# test-aetzen.net
KiCad netlist of a schematic drawn in EAGLE
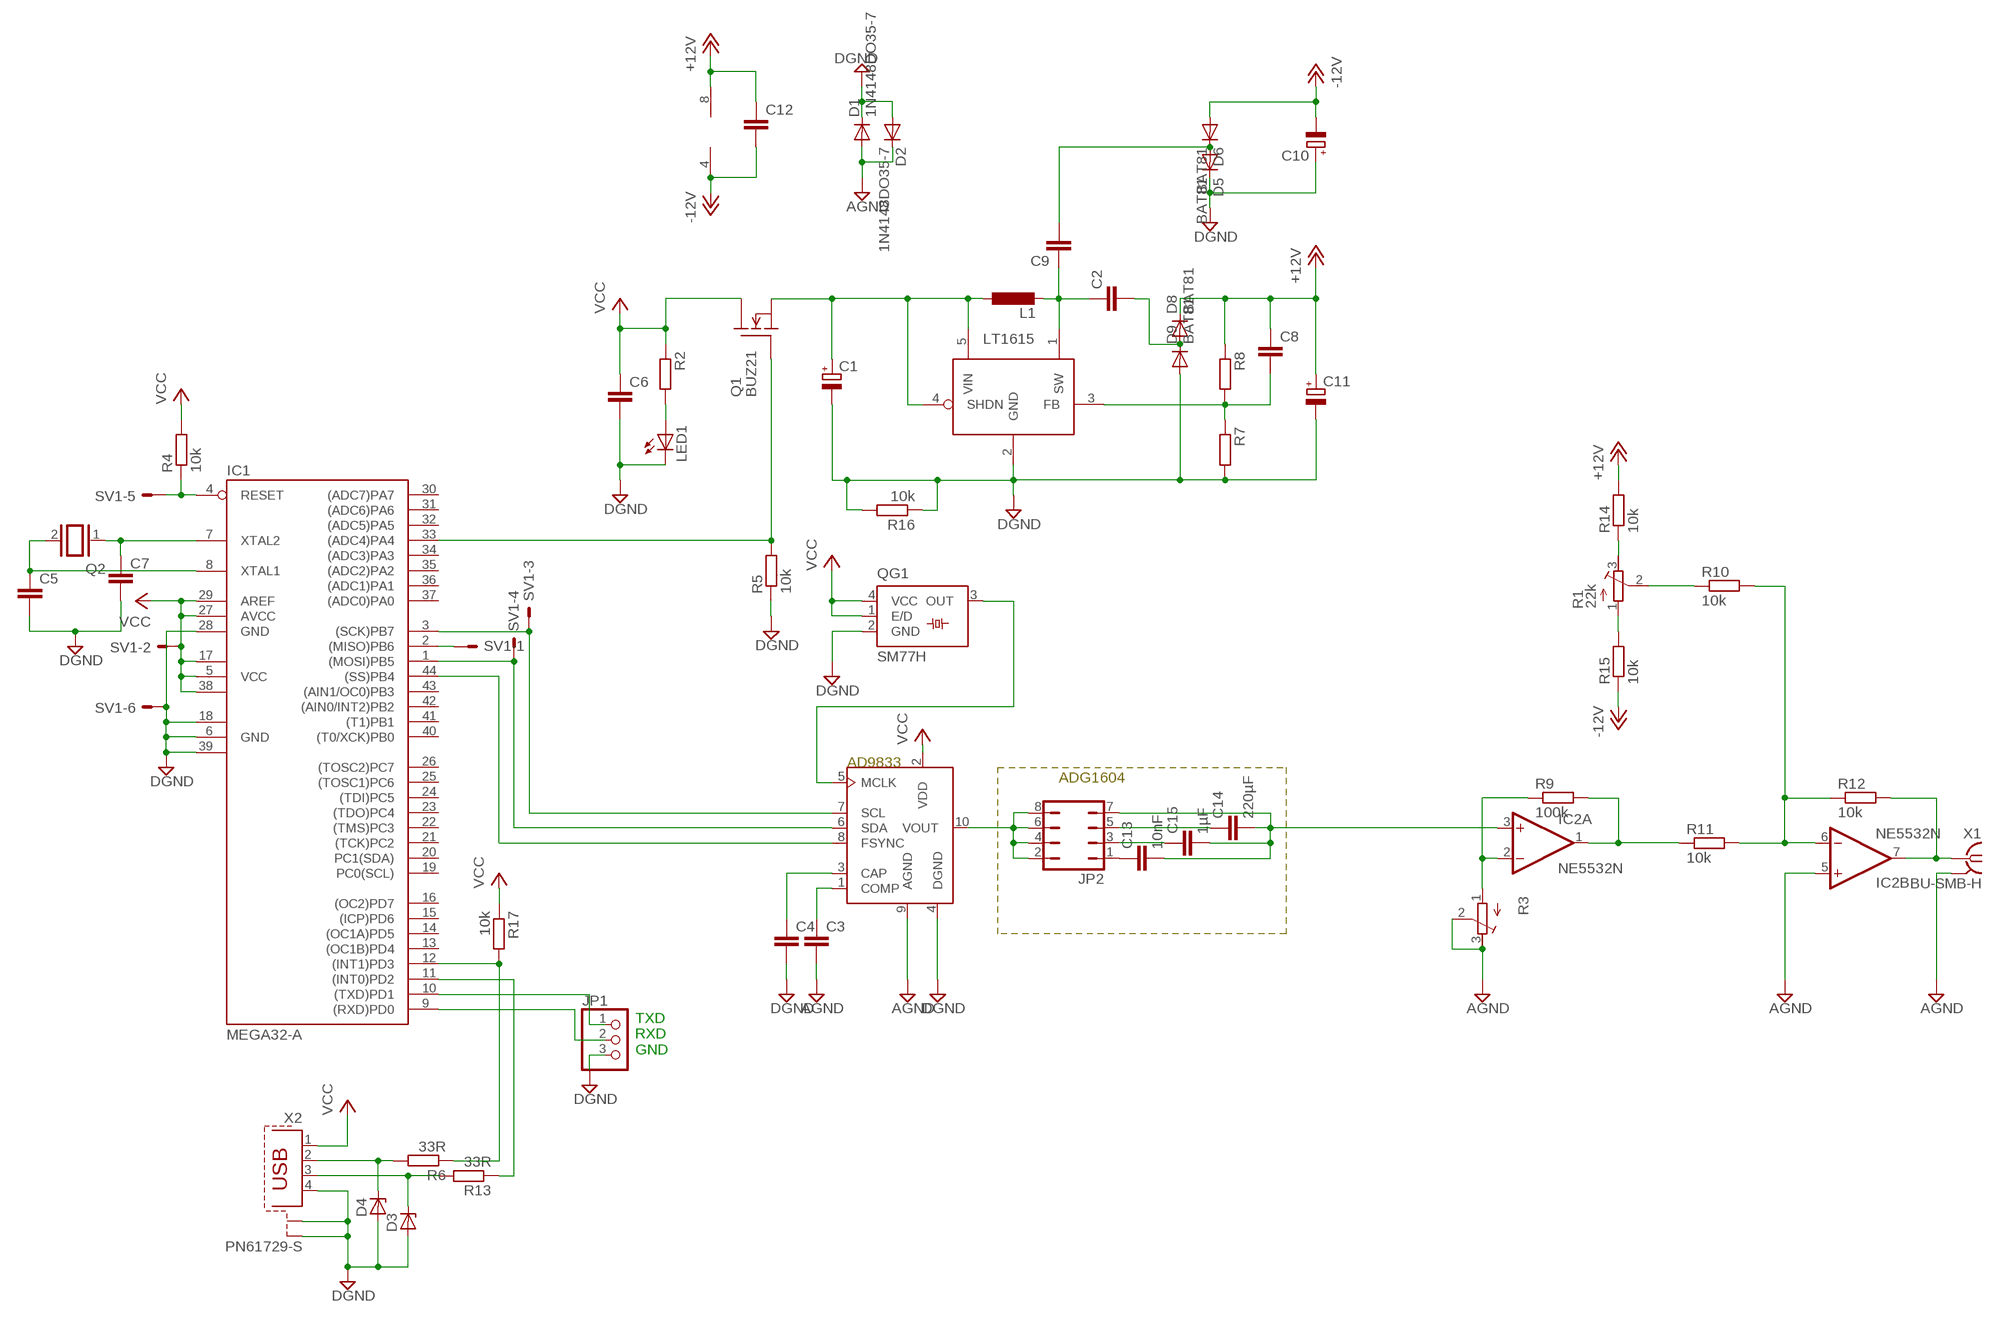
[diagram p0: schematic, sheet 1]

(export (version "E")
  (design (tool "Eeschema 10.0.6"))
  (components
    (comp (ref "C1")
      (value "CPOL-EUE3.5-8")
      (footprint "eagle-import:E3,5-8")
      (libsource (lib "eagle-import") (part "CPOL-EUE3.5-8"))
    )
    (comp (ref "C2")
      (value "C-EU025-024X044")
      (footprint "eagle-import:C025-024X044")
      (libsource (lib "eagle-import") (part "C-EU025-024X044"))
    )
    (comp (ref "C3")
      (value "C-EU025-024X044")
      (footprint "eagle-import:C025-024X044")
      (libsource (lib "eagle-import") (part "C-EU025-024X044"))
    )
    (comp (ref "C4")
      (value "C-EU025-024X044")
      (footprint "eagle-import:C025-024X044")
      (libsource (lib "eagle-import") (part "C-EU025-024X044"))
    )
    (comp (ref "C5")
      (value "C-EU025-024X044")
      (footprint "eagle-import:C025-024X044")
      (libsource (lib "eagle-import") (part "C-EU025-024X044"))
    )
    (comp (ref "C6")
      (value "C-EU025-024X044")
      (footprint "eagle-import:C025-024X044")
      (libsource (lib "eagle-import") (part "C-EU025-024X044"))
    )
    (comp (ref "C7")
      (value "C-EU025-024X044")
      (footprint "eagle-import:C025-024X044")
      (libsource (lib "eagle-import") (part "C-EU025-024X044"))
    )
    (comp (ref "C8")
      (value "C-EU025-024X044")
      (footprint "eagle-import:C025-024X044")
      (libsource (lib "eagle-import") (part "C-EU025-024X044"))
    )
    (comp (ref "C9")
      (value "C-EU025-024X044")
      (footprint "eagle-import:C025-024X044")
      (libsource (lib "eagle-import") (part "C-EU025-024X044"))
    )
    (comp (ref "C10")
      (value "CPOL-EUE3.5-8")
      (footprint "eagle-import:E3,5-8")
      (libsource (lib "eagle-import") (part "CPOL-EUE3.5-8"))
    )
    (comp (ref "C11")
      (value "CPOL-EUE3.5-8")
      (footprint "eagle-import:E3,5-8")
      (libsource (lib "eagle-import") (part "CPOL-EUE3.5-8"))
    )
    (comp (ref "C12")
      (value "C-EU025-024X044")
      (footprint "eagle-import:C025-024X044")
      (libsource (lib "eagle-import") (part "C-EU025-024X044"))
    )
    (comp (ref "C13")
      (value "10nF")
      (footprint "eagle-import:C025-024X044")
      (libsource (lib "eagle-import") (part "C-EU025-024X044"))
    )
    (comp (ref "C14")
      (value "220µF")
      (footprint "eagle-import:C025-024X044")
      (libsource (lib "eagle-import") (part "C-EU025-024X044"))
    )
    (comp (ref "C15")
      (value "1µF")
      (footprint "eagle-import:C025-024X044")
      (libsource (lib "eagle-import") (part "C-EU025-024X044"))
    )
    (comp (ref "D1")
      (value "1N4148DO35-7")
      (footprint "eagle-import:DO35-7")
      (libsource (lib "eagle-import") (part "1N4148DO35-7"))
    )
    (comp (ref "D2")
      (value "1N4148DO35-7")
      (footprint "eagle-import:DO35-7")
      (libsource (lib "eagle-import") (part "1N4148DO35-7"))
    )
    (comp (ref "D3")
      (value "ZENER-DIODEDO35Z10")
      (footprint "eagle-import:DO35Z10")
      (libsource (lib "eagle-import") (part "ZENER-DIODEDO35Z10"))
    )
    (comp (ref "D4")
      (value "ZENER-DIODEDO35Z10")
      (footprint "eagle-import:DO35Z10")
      (libsource (lib "eagle-import") (part "ZENER-DIODEDO35Z10"))
    )
    (comp (ref "D5")
      (value "BAT81")
      (footprint "eagle-import:DO34-7")
      (libsource (lib "eagle-import") (part "BAT81"))
    )
    (comp (ref "D6")
      (value "BAT81")
      (footprint "eagle-import:DO34-7")
      (libsource (lib "eagle-import") (part "BAT81"))
    )
    (comp (ref "D8")
      (value "BAT81")
      (footprint "eagle-import:DO34-7")
      (libsource (lib "eagle-import") (part "BAT81"))
    )
    (comp (ref "D9")
      (value "BAT81")
      (footprint "eagle-import:DO34-7")
      (libsource (lib "eagle-import") (part "BAT81"))
    )
    (comp (ref "IC1")
      (value "MEGA32-A")
      (footprint "eagle-import:TQFP44")
      (fields (field (name "MPN") "ATMEGA32-16AU"))
      (libsource (lib "eagle-import") (part "MEGA32-A"))
    )
    (comp (ref "IC2")
      (value "NE5532N")
      (footprint "eagle-import:DIL08")
      (libsource (lib "eagle-import") (part "NE5532N"))
    )
    (comp (ref "JP1")
      (value "PINHD-1X3")
      (footprint "eagle-import:1X03")
      (libsource (lib "eagle-import") (part "PINHD-1X3"))
    )
    (comp (ref "JP2")
      (value "JP4Q")
      (footprint "eagle-import:JP4Q")
      (libsource (lib "eagle-import") (part "JP4Q"))
    )
    (comp (ref "L1")
      (value "L-EU0207/10")
      (footprint "eagle-import:0207_10")
      (libsource (lib "eagle-import") (part "L-EU0207/10"))
    )
    (comp (ref "LED1")
      (value "LED5MM")
      (footprint "eagle-import:LED5MM")
      (libsource (lib "eagle-import") (part "LED5MM"))
    )
    (comp (ref "Q1")
      (value "BUZ21")
      (footprint "eagle-import:TO220V")
      (libsource (lib "eagle-import") (part "BUZ21"))
    )
    (comp (ref "Q2")
      (value "XTAL/S")
      (footprint "eagle-import:QS")
      (libsource (lib "eagle-import") (part "XTAL/S"))
    )
    (comp (ref "QG1")
      (value "SM77H")
      (footprint "eagle-import:SM77H")
      (libsource (lib "eagle-import") (part "SM77H"))
    )
    (comp (ref "R1")
      (value "22k")
      (footprint "eagle-import:RTRIM64Y")
      (libsource (lib "eagle-import") (part "R-TRIMM64Y"))
    )
    (comp (ref "R2")
      (value "R-EU_0207/10")
      (footprint "eagle-import:0207_10")
      (libsource (lib "eagle-import") (part "R-EU_0207/10"))
    )
    (comp (ref "R3")
      (value "R-TRIMM64Y")
      (footprint "eagle-import:RTRIM64Y")
      (libsource (lib "eagle-import") (part "R-TRIMM64Y"))
    )
    (comp (ref "R4")
      (value "10k")
      (footprint "eagle-import:M1206")
      (libsource (lib "eagle-import") (part "R-EU_M1206"))
    )
    (comp (ref "R5")
      (value "10k")
      (footprint "eagle-import:M1206")
      (libsource (lib "eagle-import") (part "R-EU_M1206"))
    )
    (comp (ref "R6")
      (value "33R")
      (footprint "eagle-import:0207_10")
      (libsource (lib "eagle-import") (part "R-EU_0207/10"))
    )
    (comp (ref "R7")
      (value "R-EU_0207/10")
      (footprint "eagle-import:0207_10")
      (libsource (lib "eagle-import") (part "R-EU_0207/10"))
    )
    (comp (ref "R8")
      (value "R-EU_0207/10")
      (footprint "eagle-import:0207_10")
      (libsource (lib "eagle-import") (part "R-EU_0207/10"))
    )
    (comp (ref "R9")
      (value "100k")
      (footprint "eagle-import:0207_10")
      (libsource (lib "eagle-import") (part "R-EU_0207/10"))
    )
    (comp (ref "R10")
      (value "10k")
      (footprint "eagle-import:M1206")
      (libsource (lib "eagle-import") (part "R-EU_M1206"))
    )
    (comp (ref "R11")
      (value "10k")
      (footprint "eagle-import:M1206")
      (libsource (lib "eagle-import") (part "R-EU_M1206"))
    )
    (comp (ref "R12")
      (value "10k")
      (footprint "eagle-import:M1206")
      (libsource (lib "eagle-import") (part "R-EU_M1206"))
    )
    (comp (ref "R13")
      (value "33R")
      (footprint "eagle-import:0207_10")
      (libsource (lib "eagle-import") (part "R-EU_0207/10"))
    )
    (comp (ref "R14")
      (value "10k")
      (footprint "eagle-import:M1206")
      (libsource (lib "eagle-import") (part "R-EU_M1206"))
    )
    (comp (ref "R15")
      (value "10k")
      (footprint "eagle-import:M1206")
      (libsource (lib "eagle-import") (part "R-EU_M1206"))
    )
    (comp (ref "R16")
      (value "10k")
      (footprint "eagle-import:M1206")
      (libsource (lib "eagle-import") (part "R-EU_M1206"))
    )
    (comp (ref "R17")
      (value "10k")
      (footprint "eagle-import:M1206")
      (libsource (lib "eagle-import") (part "R-EU_M1206"))
    )
    (comp (ref "SV1")
      (value "ML6E")
      (footprint "eagle-import:ML6")
      (libsource (lib "eagle-import") (part "ML6?E"))
    )
    (comp (ref "U$1")
      (value "AD9833-P")
      (footprint "eagle-import:DIL10")
      (libsource (lib "eagle-import") (part "AD9833-P"))
    )
    (comp (ref "U$2")
      (value "LT1615")
      (footprint "eagle-import:SOT23-5")
      (libsource (lib "eagle-import") (part "LT1615"))
    )
    (comp (ref "X1")
      (value "BU-SMB-H")
      (footprint "eagle-import:BU-SMB-H")
      (libsource (lib "eagle-import") (part "BU-SMB-H"))
    )
    (comp (ref "X2")
      (value "PN61729-S")
      (footprint "eagle-import:PN61729-S")
      (libsource (lib "eagle-import") (part "PN61729-S"))
    )
  )
  (nets
    (net (code "1") (name "+12V") (class "Default")
      (node (ref "C11") (pin "+") (pinfunction "+_+") (pintype "passive"))
      (node (ref "C12") (pin "1") (pinfunction "1_1") (pintype "passive"))
      (node (ref "C8") (pin "1") (pinfunction "1_1") (pintype "passive"))
      (node (ref "D8") (pin "C") (pinfunction "C_C") (pintype "passive"))
      (node (ref "IC2") (pin "8") (pinfunction "V+_8") (pintype "power_in"))
      (node (ref "R14") (pin "2") (pinfunction "2_2") (pintype "passive"))
      (node (ref "R8") (pin "1") (pinfunction "1_1") (pintype "passive"))
    )
    (net (code "2") (name "-12V") (class "Default")
      (node (ref "C10") (pin "-") (pinfunction "-_-") (pintype "passive"))
      (node (ref "C12") (pin "2") (pinfunction "2_2") (pintype "passive"))
      (node (ref "D6") (pin "A") (pinfunction "A_A") (pintype "passive"))
      (node (ref "IC2") (pin "4") (pinfunction "V-_4") (pintype "power_in"))
      (node (ref "R15") (pin "1") (pinfunction "1_1") (pintype "passive"))
    )
    (net (code "3") (name "AGND") (class "Default")
      (node (ref "C3") (pin "2") (pinfunction "2_2") (pintype "passive"))
      (node (ref "D1") (pin "A") (pinfunction "A_A") (pintype "passive"))
      (node (ref "D2") (pin "C") (pinfunction "C_C") (pintype "passive"))
      (node (ref "IC2") (pin "5") (pinfunction "+IN_5") (pintype "input"))
      (node (ref "R3") (pin "2") (pinfunction "S_2") (pintype "passive"))
      (node (ref "R3") (pin "3") (pinfunction "E_3") (pintype "passive"))
      (node (ref "U$1") (pin "9") (pinfunction "AGND_9") (pintype "bidirectional"))
      (node (ref "X1") (pin "2") (pinfunction "2_2") (pintype "passive"))
      (node (ref "X1") (pin "3") (pinfunction "2_3") (pintype "passive"))
      (node (ref "X1") (pin "4") (pinfunction "2_4") (pintype "passive"))
      (node (ref "X1") (pin "5") (pinfunction "2_5") (pintype "passive"))
    )
    (net (code "4") (name "DGND") (class "Default")
      (node (ref "C1") (pin "-") (pinfunction "-_-") (pintype "passive"))
      (node (ref "C10") (pin "+") (pinfunction "+_+") (pintype "passive"))
      (node (ref "C11") (pin "-") (pinfunction "-_-") (pintype "passive"))
      (node (ref "C4") (pin "2") (pinfunction "2_2") (pintype "passive"))
      (node (ref "C5") (pin "2") (pinfunction "2_2") (pintype "passive"))
      (node (ref "C6") (pin "2") (pinfunction "2_2") (pintype "passive"))
      (node (ref "C7") (pin "2") (pinfunction "2_2") (pintype "passive"))
      (node (ref "D1") (pin "C") (pinfunction "C_C") (pintype "passive"))
      (node (ref "D2") (pin "A") (pinfunction "A_A") (pintype "passive"))
      (node (ref "D3") (pin "A") (pinfunction "A_A") (pintype "passive"))
      (node (ref "D4") (pin "A") (pinfunction "A_A") (pintype "passive"))
      (node (ref "D5") (pin "C") (pinfunction "C_C") (pintype "passive"))
      (node (ref "D9") (pin "A") (pinfunction "A_A") (pintype "passive"))
      (node (ref "IC1") (pin "18") (pinfunction "GND1_18") (pintype "power_in"))
      (node (ref "IC1") (pin "28") (pinfunction "GND_28") (pintype "power_in"))
      (node (ref "IC1") (pin "39") (pinfunction "GND2_39") (pintype "power_in"))
      (node (ref "IC1") (pin "6") (pinfunction "GND_6") (pintype "power_in"))
      (node (ref "JP1") (pin "3") (pinfunction "3_3") (pintype "passive"))
      (node (ref "LED1") (pin "K") (pinfunction "C_K") (pintype "passive"))
      (node (ref "QG1") (pin "2") (pinfunction "GND_2") (pintype "power_in"))
      (node (ref "R16") (pin "1") (pinfunction "1_1") (pintype "passive"))
      (node (ref "R16") (pin "2") (pinfunction "2_2") (pintype "passive"))
      (node (ref "R5") (pin "1") (pinfunction "1_1") (pintype "passive"))
      (node (ref "R7") (pin "2") (pinfunction "2_2") (pintype "passive"))
      (node (ref "SV1") (pin "6") (pinfunction "S_6") (pintype "passive"))
      (node (ref "U$1") (pin "4") (pinfunction "DGND_4") (pintype "bidirectional"))
      (node (ref "U$2") (pin "2") (pinfunction "GND_2") (pintype "bidirectional"))
      (node (ref "X2") (pin "4") (pinfunction "4_4") (pintype "passive"))
      (node (ref "X2") (pin "S1") (pinfunction "S1_S1") (pintype "passive"))
      (node (ref "X2") (pin "S2") (pinfunction "S2_S2") (pintype "passive"))
    )
    (net (code "5") (name "Net-(C2-Pad2)") (class "Default")
      (node (ref "C2") (pin "2") (pinfunction "2_2") (pintype "passive"))
      (node (ref "D8") (pin "A") (pinfunction "A_A") (pintype "passive"))
      (node (ref "D9") (pin "C") (pinfunction "C_C") (pintype "passive"))
    )
    (net (code "6") (name "Net-(C9-Pad2)") (class "Default")
      (node (ref "C9") (pin "2") (pinfunction "2_2") (pintype "passive"))
      (node (ref "D5") (pin "A") (pinfunction "A_A") (pintype "passive"))
      (node (ref "D6") (pin "C") (pinfunction "C_C") (pintype "passive"))
    )
    (net (code "7") (name "Net-(C13-Pad1)") (class "Default")
      (node (ref "C13") (pin "1") (pinfunction "1_1") (pintype "passive"))
      (node (ref "JP2") (pin "1") (pinfunction "1_1") (pintype "passive"))
    )
    (net (code "8") (name "Net-(C14-Pad1)") (class "Default")
      (node (ref "C14") (pin "1") (pinfunction "1_1") (pintype "passive"))
      (node (ref "JP2") (pin "5") (pinfunction "5_5") (pintype "passive"))
    )
    (net (code "9") (name "Net-(C15-Pad1)") (class "Default")
      (node (ref "C15") (pin "1") (pinfunction "1_1") (pintype "passive"))
      (node (ref "JP2") (pin "3") (pinfunction "3_3") (pintype "passive"))
    )
    (net (code "10") (name "Net-(D3-PadC)") (class "Default")
      (node (ref "D3") (pin "C") (pinfunction "C_C") (pintype "passive"))
      (node (ref "R13") (pin "2") (pinfunction "2_2") (pintype "passive"))
      (node (ref "X2") (pin "3") (pinfunction "3_3") (pintype "passive"))
    )
    (net (code "11") (name "Net-(D4-PadC)") (class "Default")
      (node (ref "D4") (pin "C") (pinfunction "C_C") (pintype "passive"))
      (node (ref "R6") (pin "2") (pinfunction "2_2") (pintype "passive"))
      (node (ref "X2") (pin "2") (pinfunction "2_2") (pintype "passive"))
    )
    (net (code "12") (name "Net-(IC1-(ADC4)PA4)") (class "Default")
      (node (ref "IC1") (pin "33") (pinfunction "(ADC4)PA4_33") (pintype "bidirectional"))
      (node (ref "Q1") (pin "1") (pinfunction "G_1") (pintype "passive"))
      (node (ref "R5") (pin "2") (pinfunction "2_2") (pintype "passive"))
    )
    (net (code "13") (name "Net-(IC1-(INT0)PD2)") (class "Default")
      (node (ref "IC1") (pin "11") (pinfunction "(INT0)PD2_11") (pintype "bidirectional"))
      (node (ref "R13") (pin "1") (pinfunction "1_1") (pintype "passive"))
    )
    (net (code "14") (name "Net-(IC1-(INT1)PD3)") (class "Default")
      (node (ref "IC1") (pin "12") (pinfunction "(INT1)PD3_12") (pintype "bidirectional"))
      (node (ref "R17") (pin "2") (pinfunction "2_2") (pintype "passive"))
      (node (ref "R6") (pin "1") (pinfunction "1_1") (pintype "passive"))
    )
    (net (code "15") (name "Net-(IC1-(MISO)PB6)") (class "Default")
      (node (ref "IC1") (pin "2") (pinfunction "(MISO)PB6_2") (pintype "bidirectional"))
      (node (ref "SV1") (pin "1") (pinfunction "S_1") (pintype "passive"))
    )
    (net (code "16") (name "Net-(IC1-(MOSI)PB5)") (class "Default")
      (node (ref "IC1") (pin "1") (pinfunction "(MOSI)PB5_1") (pintype "bidirectional"))
      (node (ref "SV1") (pin "4") (pinfunction "S_4") (pintype "passive"))
      (node (ref "U$1") (pin "6") (pinfunction "SDA_6") (pintype "bidirectional"))
    )
    (net (code "17") (name "Net-(IC1-(RXD)PD0)") (class "Default")
      (node (ref "IC1") (pin "9") (pinfunction "(RXD)PD0_9") (pintype "bidirectional"))
      (node (ref "JP1") (pin "2") (pinfunction "2_2") (pintype "passive"))
    )
    (net (code "18") (name "Net-(IC1-(SCK)PB7)") (class "Default")
      (node (ref "IC1") (pin "3") (pinfunction "(SCK)PB7_3") (pintype "bidirectional"))
      (node (ref "SV1") (pin "3") (pinfunction "S_3") (pintype "passive"))
      (node (ref "U$1") (pin "7") (pinfunction "SCL_7") (pintype "bidirectional"))
    )
    (net (code "19") (name "Net-(IC1-(SS)PB4)") (class "Default")
      (node (ref "IC1") (pin "44") (pinfunction "(SS)PB4_44") (pintype "bidirectional"))
      (node (ref "U$1") (pin "8") (pinfunction "FSYNC_8") (pintype "bidirectional"))
    )
    (net (code "20") (name "Net-(IC1-(TXD)PD1)") (class "Default")
      (node (ref "IC1") (pin "10") (pinfunction "(TXD)PD1_10") (pintype "bidirectional"))
      (node (ref "JP1") (pin "1") (pinfunction "1_1") (pintype "passive"))
    )
    (net (code "21") (name "Net-(IC1-RESET)") (class "Default")
      (node (ref "IC1") (pin "4") (pinfunction "RESET_4") (pintype "input"))
      (node (ref "R4") (pin "1") (pinfunction "1_1") (pintype "passive"))
      (node (ref "SV1") (pin "5") (pinfunction "S_5") (pintype "passive"))
    )
    (net (code "22") (name "Net-(IC1-XTAL1)") (class "Default")
      (node (ref "C5") (pin "1") (pinfunction "1_1") (pintype "passive"))
      (node (ref "IC1") (pin "8") (pinfunction "XTAL1_8") (pintype "bidirectional"))
      (node (ref "Q2") (pin "2") (pinfunction "2_2") (pintype "passive"))
    )
    (net (code "23") (name "Net-(IC1-XTAL2)") (class "Default")
      (node (ref "C7") (pin "1") (pinfunction "1_1") (pintype "passive"))
      (node (ref "IC1") (pin "7") (pinfunction "XTAL2_7") (pintype "bidirectional"))
      (node (ref "Q2") (pin "1") (pinfunction "1_1") (pintype "passive"))
    )
    (net (code "24") (name "Net-(IC2A-+IN)") (class "Default")
      (node (ref "C13") (pin "2") (pinfunction "2_2") (pintype "passive"))
      (node (ref "C14") (pin "2") (pinfunction "2_2") (pintype "passive"))
      (node (ref "C15") (pin "2") (pinfunction "2_2") (pintype "passive"))
      (node (ref "IC2") (pin "3") (pinfunction "+IN_3") (pintype "input"))
      (node (ref "JP2") (pin "7") (pinfunction "7_7") (pintype "passive"))
    )
    (net (code "25") (name "Net-(IC2A--IN)") (class "Default")
      (node (ref "IC2") (pin "2") (pinfunction "-IN_2") (pintype "input"))
      (node (ref "R3") (pin "1") (pinfunction "A_1") (pintype "passive"))
      (node (ref "R9") (pin "1") (pinfunction "1_1") (pintype "passive"))
    )
    (net (code "26") (name "Net-(IC2A-OUT)") (class "Default")
      (node (ref "IC2") (pin "1") (pinfunction "OUT_1") (pintype "output"))
      (node (ref "R11") (pin "1") (pinfunction "1_1") (pintype "passive"))
      (node (ref "R9") (pin "2") (pinfunction "2_2") (pintype "passive"))
    )
    (net (code "27") (name "Net-(IC2B--IN)") (class "Default")
      (node (ref "IC2") (pin "6") (pinfunction "-IN_6") (pintype "input"))
      (node (ref "R10") (pin "2") (pinfunction "2_2") (pintype "passive"))
      (node (ref "R11") (pin "2") (pinfunction "2_2") (pintype "passive"))
      (node (ref "R12") (pin "1") (pinfunction "1_1") (pintype "passive"))
    )
    (net (code "28") (name "Net-(IC2B-OUT)") (class "Default")
      (node (ref "IC2") (pin "7") (pinfunction "OUT_7") (pintype "output"))
      (node (ref "R12") (pin "2") (pinfunction "2_2") (pintype "passive"))
      (node (ref "X1") (pin "1") (pinfunction "1_1") (pintype "passive"))
    )
    (net (code "29") (name "Net-(LED1-PadA)") (class "Default")
      (node (ref "LED1") (pin "A") (pinfunction "A_A") (pintype "passive"))
      (node (ref "R2") (pin "2") (pinfunction "2_2") (pintype "passive"))
    )
    (net (code "30") (name "Net-(Q1-S)") (class "Default")
      (node (ref "C1") (pin "+") (pinfunction "+_+") (pintype "passive"))
      (node (ref "L1") (pin "1") (pinfunction "1_1") (pintype "passive"))
      (node (ref "Q1") (pin "3") (pinfunction "S_3") (pintype "passive"))
      (node (ref "U$2") (pin "4") (pinfunction "SHDN_4") (pintype "bidirectional"))
      (node (ref "U$2") (pin "5") (pinfunction "VIN_5") (pintype "bidirectional"))
    )
    (net (code "31") (name "Net-(QG1-OUT)") (class "Default")
      (node (ref "QG1") (pin "3") (pinfunction "OUT_3") (pintype "output"))
      (node (ref "U$1") (pin "5") (pinfunction "MCLK_5") (pintype "bidirectional"))
    )
    (net (code "32") (name "Net-(R1-A)") (class "Default")
      (node (ref "R1") (pin "1") (pinfunction "A_1") (pintype "passive"))
      (node (ref "R15") (pin "2") (pinfunction "2_2") (pintype "passive"))
    )
    (net (code "33") (name "Net-(R1-E)") (class "Default")
      (node (ref "R1") (pin "3") (pinfunction "E_3") (pintype "passive"))
      (node (ref "R14") (pin "1") (pinfunction "1_1") (pintype "passive"))
    )
    (net (code "34") (name "Net-(R1-S)") (class "Default")
      (node (ref "R1") (pin "2") (pinfunction "S_2") (pintype "passive"))
      (node (ref "R10") (pin "1") (pinfunction "1_1") (pintype "passive"))
    )
    (net (code "35") (name "Net-(U$1-CAP)") (class "Default")
      (node (ref "C4") (pin "1") (pinfunction "1_1") (pintype "passive"))
      (node (ref "U$1") (pin "3") (pinfunction "CAP_3") (pintype "bidirectional"))
    )
    (net (code "36") (name "Net-(U$1-COMP)") (class "Default")
      (node (ref "C3") (pin "1") (pinfunction "1_1") (pintype "passive"))
      (node (ref "U$1") (pin "1") (pinfunction "COMP_1") (pintype "bidirectional"))
    )
    (net (code "37") (name "Net-(U$1-VOUT)") (class "Default")
      (node (ref "JP2") (pin "2") (pinfunction "2_2") (pintype "passive"))
      (node (ref "JP2") (pin "4") (pinfunction "4_4") (pintype "passive"))
      (node (ref "JP2") (pin "6") (pinfunction "6_6") (pintype "passive"))
      (node (ref "JP2") (pin "8") (pinfunction "8_8") (pintype "passive"))
      (node (ref "U$1") (pin "10") (pinfunction "VOUT_10") (pintype "bidirectional"))
    )
    (net (code "38") (name "Net-(U$2-FB)") (class "Default")
      (node (ref "C8") (pin "2") (pinfunction "2_2") (pintype "passive"))
      (node (ref "R7") (pin "1") (pinfunction "1_1") (pintype "passive"))
      (node (ref "R8") (pin "2") (pinfunction "2_2") (pintype "passive"))
      (node (ref "U$2") (pin "3") (pinfunction "FB_3") (pintype "bidirectional"))
    )
    (net (code "39") (name "Net-(U$2-SW)") (class "Default")
      (node (ref "C2") (pin "1") (pinfunction "1_1") (pintype "passive"))
      (node (ref "C9") (pin "1") (pinfunction "1_1") (pintype "passive"))
      (node (ref "L1") (pin "2") (pinfunction "2_2") (pintype "passive"))
      (node (ref "U$2") (pin "1") (pinfunction "SW_1") (pintype "bidirectional"))
    )
    (net (code "40") (name "VCC") (class "Default")
      (node (ref "C6") (pin "1") (pinfunction "1_1") (pintype "passive"))
      (node (ref "IC1") (pin "17") (pinfunction "VCC1_17") (pintype "power_in"))
      (node (ref "IC1") (pin "27") (pinfunction "AVCC_27") (pintype "power_in"))
      (node (ref "IC1") (pin "29") (pinfunction "AREF_29") (pintype "passive"))
      (node (ref "IC1") (pin "38") (pinfunction "VCC2_38") (pintype "power_in"))
      (node (ref "IC1") (pin "5") (pinfunction "VCC_5") (pintype "power_in"))
      (node (ref "Q1") (pin "2") (pinfunction "D_2") (pintype "passive"))
      (node (ref "QG1") (pin "1") (pinfunction "E/D_1") (pintype "input"))
      (node (ref "QG1") (pin "4") (pinfunction "VCC_4") (pintype "power_in"))
      (node (ref "R17") (pin "1") (pinfunction "1_1") (pintype "passive"))
      (node (ref "R2") (pin "1") (pinfunction "1_1") (pintype "passive"))
      (node (ref "R4") (pin "2") (pinfunction "2_2") (pintype "passive"))
      (node (ref "SV1") (pin "2") (pinfunction "S_2") (pintype "passive"))
      (node (ref "U$1") (pin "2") (pinfunction "VDD_2") (pintype "bidirectional"))
      (node (ref "X2") (pin "1") (pinfunction "1_1") (pintype "passive"))
    )
    (net (code "41") (name "unconnected-(IC1-(ADC0)PA0-Pad37)") (class "Default")
      (node (ref "IC1") (pin "37") (pinfunction "(ADC0)PA0_37") (pintype "bidirectional"))
    )
    (net (code "42") (name "unconnected-(IC1-(ADC1)PA1-Pad36)") (class "Default")
      (node (ref "IC1") (pin "36") (pinfunction "(ADC1)PA1_36") (pintype "bidirectional"))
    )
    (net (code "43") (name "unconnected-(IC1-(ADC2)PA2-Pad35)") (class "Default")
      (node (ref "IC1") (pin "35") (pinfunction "(ADC2)PA2_35") (pintype "bidirectional"))
    )
    (net (code "44") (name "unconnected-(IC1-(ADC3)PA3-Pad34)") (class "Default")
      (node (ref "IC1") (pin "34") (pinfunction "(ADC3)PA3_34") (pintype "bidirectional"))
    )
    (net (code "45") (name "unconnected-(IC1-(ADC5)PA5-Pad32)") (class "Default")
      (node (ref "IC1") (pin "32") (pinfunction "(ADC5)PA5_32") (pintype "bidirectional"))
    )
    (net (code "46") (name "unconnected-(IC1-(ADC6)PA6-Pad31)") (class "Default")
      (node (ref "IC1") (pin "31") (pinfunction "(ADC6)PA6_31") (pintype "bidirectional"))
    )
    (net (code "47") (name "unconnected-(IC1-(ADC7)PA7-Pad30)") (class "Default")
      (node (ref "IC1") (pin "30") (pinfunction "(ADC7)PA7_30") (pintype "bidirectional"))
    )
    (net (code "48") (name "unconnected-(IC1-(AIN0{slash}INT2)PB2-Pad42)") (class "Default")
      (node (ref "IC1") (pin "42") (pinfunction "(AIN0/INT2)PB2_42") (pintype "bidirectional"))
    )
    (net (code "49") (name "unconnected-(IC1-(AIN1{slash}OC0)PB3-Pad43)") (class "Default")
      (node (ref "IC1") (pin "43") (pinfunction "(AIN1/OC0)PB3_43") (pintype "bidirectional"))
    )
    (net (code "50") (name "unconnected-(IC1-(ICP)PD6-Pad15)") (class "Default")
      (node (ref "IC1") (pin "15") (pinfunction "(ICP)PD6_15") (pintype "bidirectional"))
    )
    (net (code "51") (name "unconnected-(IC1-(OC1A)PD5-Pad14)") (class "Default")
      (node (ref "IC1") (pin "14") (pinfunction "(OC1A)PD5_14") (pintype "bidirectional"))
    )
    (net (code "52") (name "unconnected-(IC1-(OC1B)PD4-Pad13)") (class "Default")
      (node (ref "IC1") (pin "13") (pinfunction "(OC1B)PD4_13") (pintype "bidirectional"))
    )
    (net (code "53") (name "unconnected-(IC1-(OC2)PD7-Pad16)") (class "Default")
      (node (ref "IC1") (pin "16") (pinfunction "(OC2)PD7_16") (pintype "bidirectional"))
    )
    (net (code "54") (name "unconnected-(IC1-(T0{slash}XCK)PB0-Pad40)") (class "Default")
      (node (ref "IC1") (pin "40") (pinfunction "(T0/XCK)PB0_40") (pintype "bidirectional"))
    )
    (net (code "55") (name "unconnected-(IC1-(T1)PB1-Pad41)") (class "Default")
      (node (ref "IC1") (pin "41") (pinfunction "(T1)PB1_41") (pintype "bidirectional"))
    )
    (net (code "56") (name "unconnected-(IC1-(TCK)PC2-Pad21)") (class "Default")
      (node (ref "IC1") (pin "21") (pinfunction "(TCK)PC2_21") (pintype "bidirectional"))
    )
    (net (code "57") (name "unconnected-(IC1-(TDI)PC5-Pad24)") (class "Default")
      (node (ref "IC1") (pin "24") (pinfunction "(TDI)PC5_24") (pintype "bidirectional"))
    )
    (net (code "58") (name "unconnected-(IC1-(TDO)PC4-Pad23)") (class "Default")
      (node (ref "IC1") (pin "23") (pinfunction "(TDO)PC4_23") (pintype "bidirectional"))
    )
    (net (code "59") (name "unconnected-(IC1-(TMS)PC3-Pad22)") (class "Default")
      (node (ref "IC1") (pin "22") (pinfunction "(TMS)PC3_22") (pintype "bidirectional"))
    )
    (net (code "60") (name "unconnected-(IC1-(TOSC1)PC6-Pad25)") (class "Default")
      (node (ref "IC1") (pin "25") (pinfunction "(TOSC1)PC6_25") (pintype "bidirectional"))
    )
    (net (code "61") (name "unconnected-(IC1-(TOSC2)PC7-Pad26)") (class "Default")
      (node (ref "IC1") (pin "26") (pinfunction "(TOSC2)PC7_26") (pintype "bidirectional"))
    )
    (net (code "62") (name "unconnected-(IC1-PC0(SCL)-Pad19)") (class "Default")
      (node (ref "IC1") (pin "19") (pinfunction "PC0(SCL)_19") (pintype "bidirectional"))
    )
    (net (code "63") (name "unconnected-(IC1-PC1(SDA)-Pad20)") (class "Default")
      (node (ref "IC1") (pin "20") (pinfunction "PC1(SDA)_20") (pintype "bidirectional"))
    )
  )
)
